# SCH_NewRainSensor_2024-05-19.net
KiCad netlist of a schematic drawn in EasyEDA
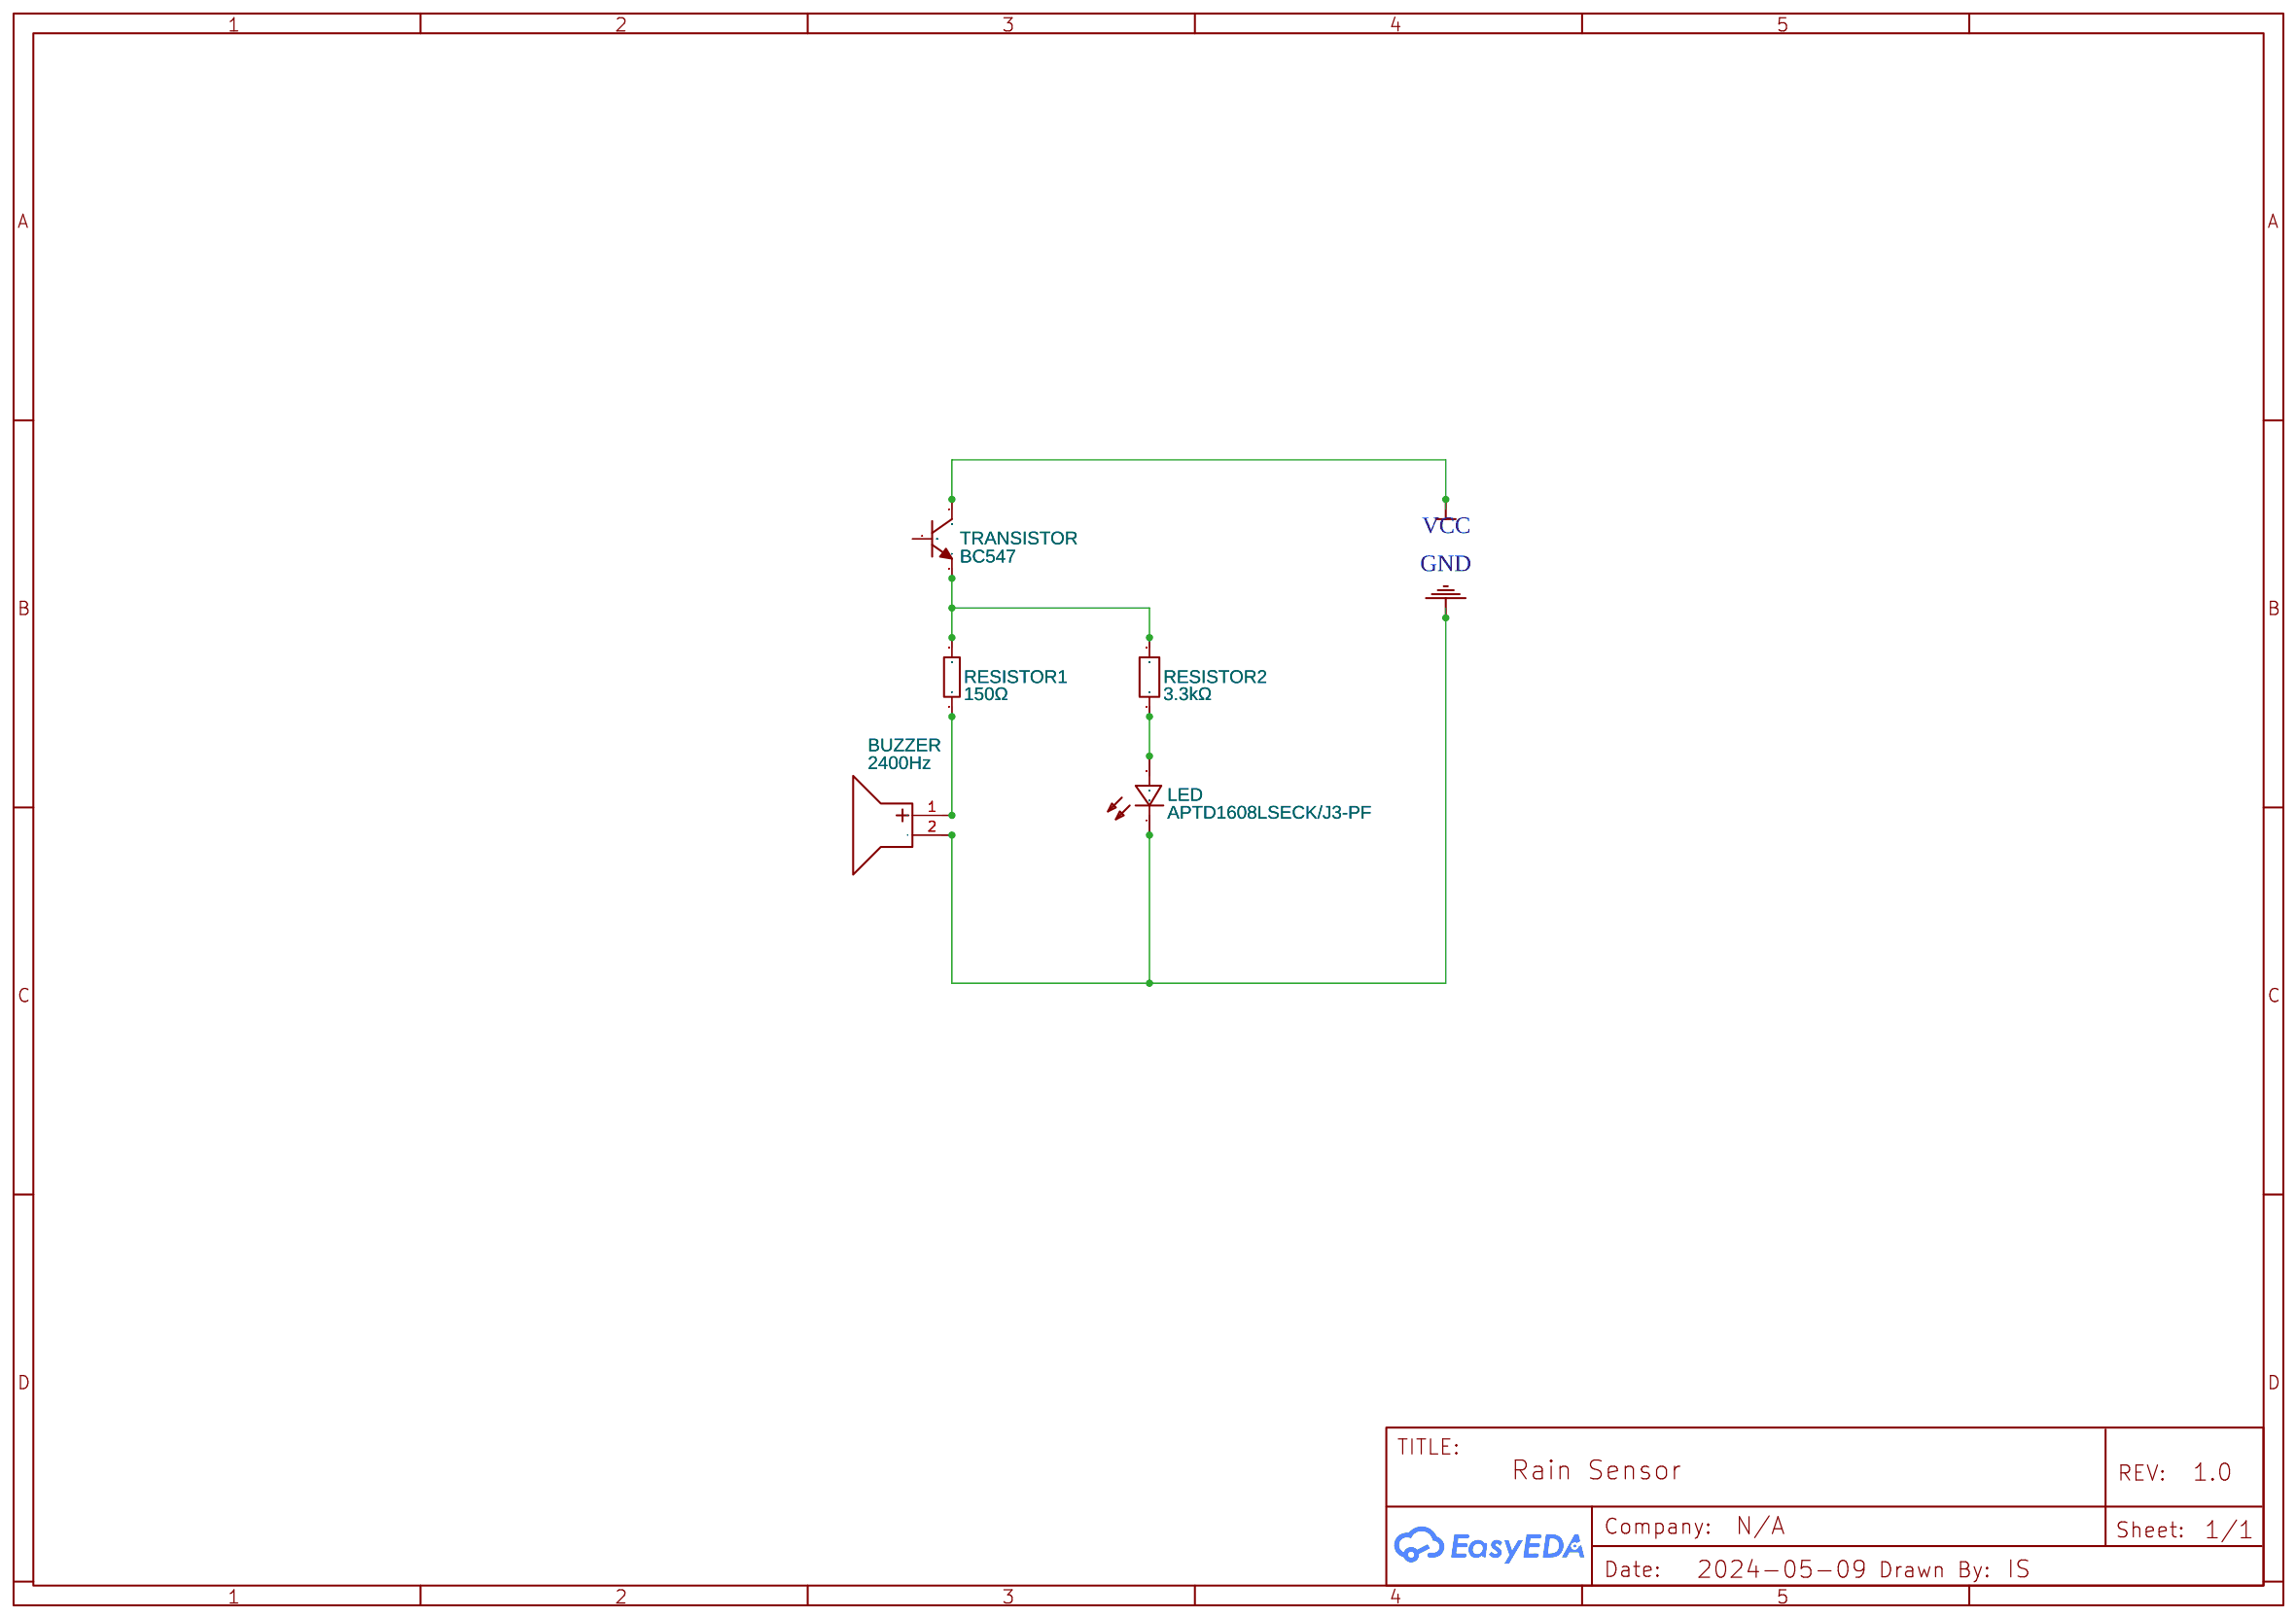
[diagram p0: schematic sheet]

(export (version "E")
  (design (tool "Eeschema 10.0.6"))
  (components
    (comp (ref "BUZZER")
      (value "2400Hz")
      (fields (field (name "Manufacturer Part") "FUET-1365-5V") (field (name "Manufacturer") "FUET(福声科技)"))
      (libsource (lib "") (part "FUET-1365-5V"))
    )
    (comp (ref "LED")
      (value "APTD1608LSECK/J3-PF")
      (fields (field (name "Manufacturer") "Kingbright"))
      (libsource (lib "") (part "APTD1608LSECK/J3-PF"))
    )
    (comp (ref "RESISTOR1")
      (value "150Ω")
      (fields (field (name "Manufacturer Part") "AECR1206F150RK9") (field (name "Manufacturer") "RESI(开步睿思）"))
      (libsource (lib "") (part "AECR1206F150RK9"))
    )
    (comp (ref "RESISTOR2")
      (value "3.3kΩ")
      (fields (field (name "Manufacturer Part") "ERJ3GEYJ332V") (field (name "Manufacturer") "PANASONIC(松下)"))
      (libsource (lib "") (part "ERJ3GEYJ332V"))
    )
    (comp (ref "TRANSISTOR")
      (value "BC547")
      (fields
        (field (name "Manufacturer Part") "BC547(RANGE:420-800)")
        (field (name "Manufacturer") "CJ(江苏长电/长晶)")
      )
      (libsource (lib "") (part "BC547"))
    )
  )
  (nets
    (net (code "1") (name "GND") (class "Default")
      (node (ref "BUZZER") (pin "2") (pinfunction "-_2") (pintype "unspecified"))
      (node (ref "LED") (pin "1") (pinfunction "C_1") (pintype "unspecified"))
    )
    (net (code "2") (name "Net-(BUZZER-+)") (class "Default")
      (node (ref "BUZZER") (pin "1") (pinfunction "+_1") (pintype "unspecified"))
      (node (ref "RESISTOR1") (pin "1") (pinfunction "1_1") (pintype "unspecified"))
    )
    (net (code "3") (name "Net-(LED-A)") (class "Default")
      (node (ref "LED") (pin "2") (pinfunction "A_2") (pintype "unspecified"))
      (node (ref "RESISTOR2") (pin "1") (pinfunction "1_1") (pintype "unspecified"))
    )
    (net (code "4") (name "Net-(TRANSISTOR-E)") (class "Default")
      (node (ref "RESISTOR1") (pin "2") (pinfunction "2_2") (pintype "unspecified"))
      (node (ref "RESISTOR2") (pin "2") (pinfunction "2_2") (pintype "unspecified"))
      (node (ref "TRANSISTOR") (pin "3") (pinfunction "E_3") (pintype "unspecified"))
    )
    (net (code "5") (name "VCC") (class "Default")
      (node (ref "TRANSISTOR") (pin "1") (pinfunction "C_1") (pintype "unspecified"))
    )
    (net (code "6") (name "unconnected-(TRANSISTOR-B-Pad2)") (class "Default")
      (node (ref "TRANSISTOR") (pin "2") (pinfunction "B_2") (pintype "unspecified"))
    )
  )
)
